# Relays.net
KiCad netlist of a schematic drawn in Altium Designer
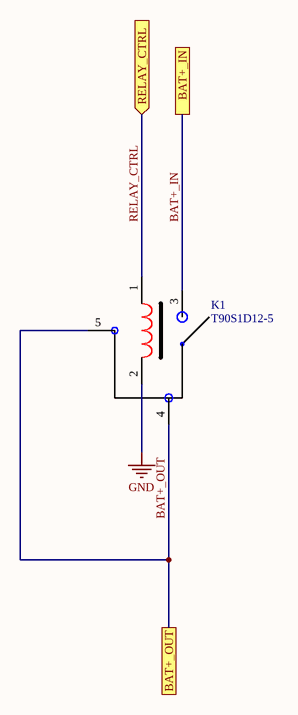
[diagram p0: Relays.SchDoc]

(export (version "E")
  (design (tool "Eeschema 10.0.6"))
  (components
    (comp (ref "K1")
      (value "T90S1D12-5")
      (footprint "T90S")
      (description "General Purpose Relays SPST-NO PCB 5 VDC")
      (fields (field (name "MANUFACTURER") "TE Connectivity"))
      (libsource (lib "TE_PCB_Relays") (part "T90S1D12-5"))
    )
  )
  (nets
    (net (code "1") (name "/BAT+_IN") (class "Default")
      (node (ref "K1") (pin "3") (pinfunction "Contact_3") (pintype "power_in"))
    )
    (net (code "2") (name "/BAT+_OUT") (class "Default")
      (node (ref "K1") (pin "4") (pinfunction "Contact_4") (pintype "power_in"))
      (node (ref "K1") (pin "5") (pinfunction "Contact_5") (pintype "power_in"))
    )
    (net (code "3") (name "/RELAY_CTRL") (class "Default")
      (node (ref "K1") (pin "1") (pinfunction "Coil_1") (pintype "passive"))
    )
    (net (code "4") (name "GND") (class "Default")
      (node (ref "K1") (pin "2") (pinfunction "Coil_2") (pintype "passive"))
    )
  )
)
